# LCD_Display-1U.net
KiCad netlist of a schematic drawn in EAGLE
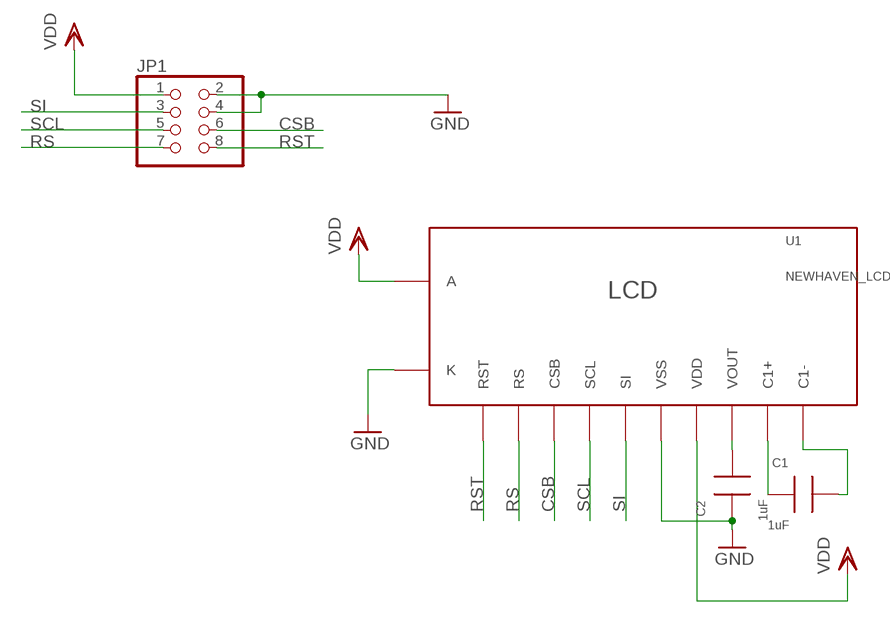
[diagram p0: schematic, sheet 1]

(export (version "E")
  (design (tool "Eeschema 10.0.6"))
  (components
    (comp (ref "C1")
      (value "1uF")
      (footprint "eagle-import:0805")
      (fields (field (name "PARTNO") "CL21A105KBCLNNC"))
      (libsource (lib "eagle-import") (part "CAP0805"))
    )
    (comp (ref "C2")
      (value "1uF")
      (footprint "eagle-import:0805")
      (fields (field (name "PARTNO") "CL21A105KBCLNNC"))
      (libsource (lib "eagle-import") (part "CAP0805"))
    )
    (comp (ref "JP1")
      (value "PINHD-2X4SMT")
      (footprint "eagle-import:2X4SMT")
      (fields (field (name "PARTNO") "0015912080"))
      (libsource (lib "eagle-import") (part "PINHD-2X4SMT"))
    )
    (comp (ref "U1")
      (value "NEWHAVEN_LCD")
      (footprint "eagle-import:NEWHAVEN_LCD")
      (fields
        (field (name "PARTNUM") "NHD-C0216CZ-FSW-FBW-3V3-ND")
        (field (name "PARTNO") "NHD-C0216CZ-FSW-FBW-3V3")
      )
      (libsource (lib "eagle-import") (part "NEWHAVEN_LCD"))
    )
  )
  (nets
    (net (code "1") (name "/CSB") (class "Default")
      (node (ref "JP1") (pin "6") (pinfunction "6_6") (pintype "passive"))
      (node (ref "U1") (pin "3") (pinfunction "CSB_3") (pintype "bidirectional"))
    )
    (net (code "2") (name "/RS") (class "Default")
      (node (ref "JP1") (pin "7") (pinfunction "7_7") (pintype "passive"))
      (node (ref "U1") (pin "2") (pinfunction "RS_2") (pintype "bidirectional"))
    )
    (net (code "3") (name "/RST") (class "Default")
      (node (ref "JP1") (pin "8") (pinfunction "8_8") (pintype "passive"))
      (node (ref "U1") (pin "1") (pinfunction "RST_1") (pintype "bidirectional"))
    )
    (net (code "4") (name "/SCL") (class "Default")
      (node (ref "JP1") (pin "5") (pinfunction "5_5") (pintype "passive"))
      (node (ref "U1") (pin "4") (pinfunction "SCL_4") (pintype "bidirectional"))
    )
    (net (code "5") (name "/SI") (class "Default")
      (node (ref "JP1") (pin "3") (pinfunction "3_3") (pintype "passive"))
      (node (ref "U1") (pin "5") (pinfunction "SI_5") (pintype "bidirectional"))
    )
    (net (code "6") (name "GND") (class "Default")
      (node (ref "C2") (pin "1") (pinfunction "P$1_1") (pintype "passive"))
      (node (ref "JP1") (pin "2") (pinfunction "2_2") (pintype "passive"))
      (node (ref "JP1") (pin "4") (pinfunction "4_4") (pintype "passive"))
      (node (ref "U1") (pin "6") (pinfunction "VSS_6") (pintype "bidirectional"))
      (node (ref "U1") (pin "K") (pinfunction "K_K") (pintype "bidirectional"))
    )
    (net (code "7") (name "Net-(C1-P$1)") (class "Default")
      (node (ref "C1") (pin "1") (pinfunction "P$1_1") (pintype "passive"))
      (node (ref "U1") (pin "9") (pinfunction "C1+_9") (pintype "bidirectional"))
    )
    (net (code "8") (name "Net-(C1-P$2)") (class "Default")
      (node (ref "C1") (pin "2") (pinfunction "P$2_2") (pintype "passive"))
      (node (ref "U1") (pin "10") (pinfunction "C1-_10") (pintype "bidirectional"))
    )
    (net (code "9") (name "Net-(C2-P$2)") (class "Default")
      (node (ref "C2") (pin "2") (pinfunction "P$2_2") (pintype "passive"))
      (node (ref "U1") (pin "8") (pinfunction "VOUT_8") (pintype "bidirectional"))
    )
    (net (code "10") (name "VDD") (class "Default")
      (node (ref "JP1") (pin "1") (pinfunction "1_1") (pintype "passive"))
      (node (ref "U1") (pin "7") (pinfunction "VDD_7") (pintype "bidirectional"))
      (node (ref "U1") (pin "A") (pinfunction "A_A") (pintype "bidirectional"))
    )
  )
)
